# light.net
KiCad netlist of a schematic drawn in EAGLE
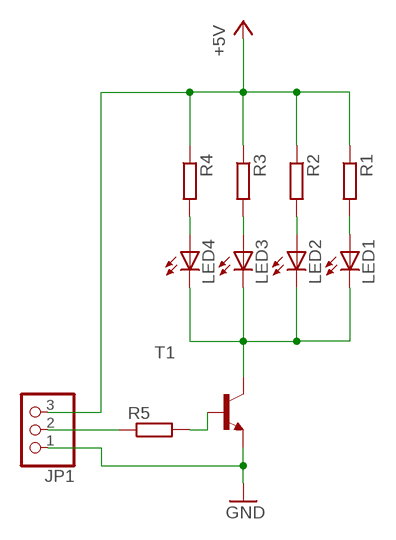
[diagram p0: schematic, sheet 1]

(export (version "E")
  (design (tool "Eeschema 10.0.6"))
  (components
    (comp (ref "JP1")
      (value "PINHD-1X3/90")
      (footprint "eagle-import:1X03_90")
      (libsource (lib "eagle-import") (part "PINHD-1X3/90"))
    )
    (comp (ref "LED1")
      (value "LED3MM")
      (footprint "eagle-import:LED3MM")
      (libsource (lib "eagle-import") (part "LED3MM"))
    )
    (comp (ref "LED2")
      (value "LED3MM")
      (footprint "eagle-import:LED3MM")
      (libsource (lib "eagle-import") (part "LED3MM"))
    )
    (comp (ref "LED3")
      (value "LED3MM")
      (footprint "eagle-import:LED3MM")
      (libsource (lib "eagle-import") (part "LED3MM"))
    )
    (comp (ref "LED4")
      (value "LED3MM")
      (footprint "eagle-import:LED3MM")
      (libsource (lib "eagle-import") (part "LED3MM"))
    )
    (comp (ref "R1")
      (value "R-EU_0207/10")
      (footprint "eagle-import:0207_10")
      (libsource (lib "eagle-import") (part "R-EU_0207/10"))
    )
    (comp (ref "R2")
      (value "R-EU_0207/10")
      (footprint "eagle-import:0207_10")
      (libsource (lib "eagle-import") (part "R-EU_0207/10"))
    )
    (comp (ref "R3")
      (value "R-EU_0207/10")
      (footprint "eagle-import:0207_10")
      (libsource (lib "eagle-import") (part "R-EU_0207/10"))
    )
    (comp (ref "R4")
      (value "R-EU_0207/10")
      (footprint "eagle-import:0207_10")
      (libsource (lib "eagle-import") (part "R-EU_0207/10"))
    )
    (comp (ref "R5")
      (value "R-EU_0207/10")
      (footprint "eagle-import:0207_10")
      (libsource (lib "eagle-import") (part "R-EU_0207/10"))
    )
    (comp (ref "T1")
      (value "-NPN-SOT223")
      (footprint "eagle-import:SOT223")
      (libsource (lib "eagle-import") (part "-NPN-SOT223"))
    )
  )
  (nets
    (net (code "1") (name "+5V") (class "Default")
      (node (ref "JP1") (pin "3") (pinfunction "3_3") (pintype "passive"))
      (node (ref "R1") (pin "1") (pinfunction "1_1") (pintype "passive"))
      (node (ref "R2") (pin "1") (pinfunction "1_1") (pintype "passive"))
      (node (ref "R3") (pin "1") (pinfunction "1_1") (pintype "passive"))
      (node (ref "R4") (pin "1") (pinfunction "1_1") (pintype "passive"))
    )
    (net (code "2") (name "GND") (class "Default")
      (node (ref "JP1") (pin "1") (pinfunction "1_1") (pintype "passive"))
      (node (ref "T1") (pin "3") (pinfunction "E_3") (pintype "passive"))
    )
    (net (code "3") (name "Net-(JP1-Pad2)") (class "Default")
      (node (ref "JP1") (pin "2") (pinfunction "2_2") (pintype "passive"))
      (node (ref "R5") (pin "1") (pinfunction "1_1") (pintype "passive"))
    )
    (net (code "4") (name "Net-(LED1-C)") (class "Default")
      (node (ref "LED1") (pin "K") (pinfunction "C_K") (pintype "passive"))
      (node (ref "LED2") (pin "K") (pinfunction "C_K") (pintype "passive"))
      (node (ref "LED3") (pin "K") (pinfunction "C_K") (pintype "passive"))
      (node (ref "LED4") (pin "K") (pinfunction "C_K") (pintype "passive"))
      (node (ref "T1") (pin "4") (pinfunction "C_4") (pintype "passive"))
    )
    (net (code "5") (name "Net-(LED1-PadA)") (class "Default")
      (node (ref "LED1") (pin "A") (pinfunction "A_A") (pintype "passive"))
      (node (ref "R1") (pin "2") (pinfunction "2_2") (pintype "passive"))
    )
    (net (code "6") (name "Net-(LED2-PadA)") (class "Default")
      (node (ref "LED2") (pin "A") (pinfunction "A_A") (pintype "passive"))
      (node (ref "R2") (pin "2") (pinfunction "2_2") (pintype "passive"))
    )
    (net (code "7") (name "Net-(LED3-PadA)") (class "Default")
      (node (ref "LED3") (pin "A") (pinfunction "A_A") (pintype "passive"))
      (node (ref "R3") (pin "2") (pinfunction "2_2") (pintype "passive"))
    )
    (net (code "8") (name "Net-(LED4-PadA)") (class "Default")
      (node (ref "LED4") (pin "A") (pinfunction "A_A") (pintype "passive"))
      (node (ref "R4") (pin "2") (pinfunction "2_2") (pintype "passive"))
    )
    (net (code "9") (name "Net-(T1-B)") (class "Default")
      (node (ref "R5") (pin "2") (pinfunction "2_2") (pintype "passive"))
      (node (ref "T1") (pin "1") (pinfunction "B_1") (pintype "passive"))
    )
  )
)
